# MakerCard.net
KiCad netlist of a schematic drawn in Altium Designer
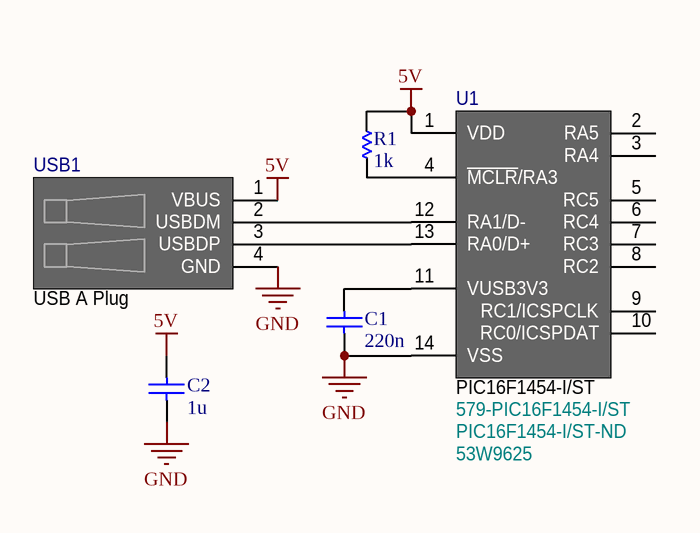
[diagram p0: MakerCard.SchDoc]

(export (version "E")
  (design (tool "Eeschema 10.0.6"))
  (components
    (comp (ref "C1")
      (value "220n")
      (footprint "CAPC1005N")
      (description "Capacitor (Semiconductor SIM Model)")
      (fields (field (name "PUBLISHER") "Altium Limited"))
      (libsource (lib "Miscellaneous Devices") (part "Cap Semi"))
    )
    (comp (ref "C2")
      (value "1u")
      (footprint "CAPC1608N")
      (description "Capacitor (Semiconductor SIM Model)")
      (fields (field (name "PUBLISHER") "Altium Limited"))
      (libsource (lib "Miscellaneous Devices") (part "Cap Semi"))
    )
    (comp (ref "R1")
      (value "1k")
      (footprint "RESC1005N")
      (description "Semiconductor Resistor")
      (fields (field (name "PUBLISHER") "Altium Limited"))
      (libsource (lib "Miscellaneous Devices") (part "Res Semi"))
    )
    (comp (ref "U1")
      (value "PIC16F1454-I/ST")
      (footprint "TSOP65P640-14AN")
      (description "8-bit Microcontrollers - MCU 7 KB Flash 512 bytes RAM 48 MHz Int Osc")
      (fields
        (field (name "MANUFACTURER") "Microchip Technology")
        (field (name "SUPPLIER PART NUMBER 1") "579-PIC16F1454-I/ST")
        (field (name "SUPPLIER PART NUMBER 2") "PIC16F1454-I/ST-ND")
        (field (name "SUPPLIER PART NUMBER 3") "53W9625")
      )
      (libsource (lib "Microchip Microcontroller 8-Bit") (part "PIC16F1454-I/ST"))
    )
    (comp (ref "USB1")
      (value "USB A Plug")
      (footprint "USB_A_EDGECONNECTOR")
      (libsource (lib "Miscellaneous Connectors") (part "USB A Plug"))
    )
  )
  (nets
    (net (code "1") (name "5V") (class "Default")
      (node (ref "C2") (pin "2") (pinfunction "2_2") (pintype "passive"))
      (node (ref "R1") (pin "2") (pinfunction "2_2") (pintype "passive"))
      (node (ref "U1") (pin "1") (pinfunction "VDD_1") (pintype "power_in"))
      (node (ref "USB1") (pin "1") (pinfunction "VBUS_1") (pintype "power_in"))
    )
    (net (code "2") (name "GND") (class "Default")
      (node (ref "C1") (pin "1") (pinfunction "1_1") (pintype "passive"))
      (node (ref "C2") (pin "1") (pinfunction "1_1") (pintype "passive"))
      (node (ref "U1") (pin "14") (pinfunction "VSS_14") (pintype "power_in"))
      (node (ref "USB1") (pin "4") (pinfunction "GND_4") (pintype "power_in"))
    )
    (net (code "3") (name "Net-(U1-RA0{slash}D+)") (class "Default")
      (node (ref "U1") (pin "13") (pinfunction "RA0/D+_13") (pintype "power_in"))
      (node (ref "USB1") (pin "3") (pinfunction "USBDP_3") (pintype "power_in"))
    )
    (net (code "4") (name "Net-(U1-RA1{slash}D-)") (class "Default")
      (node (ref "U1") (pin "12") (pinfunction "RA1/D-_12") (pintype "power_in"))
      (node (ref "USB1") (pin "2") (pinfunction "USBDM_2") (pintype "power_in"))
    )
    (net (code "5") (name "Net-(U1-VUSB3V3)") (class "Default")
      (node (ref "C1") (pin "2") (pinfunction "2_2") (pintype "passive"))
      (node (ref "U1") (pin "11") (pinfunction "VUSB3V3_11") (pintype "power_in"))
    )
    (net (code "6") (name "Net-(U1-~{MCLR}{slash}RA3)") (class "Default")
      (node (ref "R1") (pin "1") (pinfunction "1_1") (pintype "passive"))
      (node (ref "U1") (pin "4") (pinfunction "~{MCLR}/RA3_4") (pintype "power_in"))
    )
    (net (code "7") (name "unconnected-(U1-RA4-Pad3)") (class "Default")
      (node (ref "U1") (pin "3") (pinfunction "RA4_3") (pintype "power_in"))
    )
    (net (code "8") (name "unconnected-(U1-RA5-Pad2)") (class "Default")
      (node (ref "U1") (pin "2") (pinfunction "RA5_2") (pintype "power_in"))
    )
    (net (code "9") (name "unconnected-(U1-RC0{slash}ICSPDAT-Pad10)") (class "Default")
      (node (ref "U1") (pin "10") (pinfunction "RC0/ICSPDAT_10") (pintype "power_in"))
    )
    (net (code "10") (name "unconnected-(U1-RC1{slash}ICSPCLK-Pad9)") (class "Default")
      (node (ref "U1") (pin "9") (pinfunction "RC1/ICSPCLK_9") (pintype "power_in"))
    )
    (net (code "11") (name "unconnected-(U1-RC2-Pad8)") (class "Default")
      (node (ref "U1") (pin "8") (pinfunction "RC2_8") (pintype "power_in"))
    )
    (net (code "12") (name "unconnected-(U1-RC3-Pad7)") (class "Default")
      (node (ref "U1") (pin "7") (pinfunction "RC3_7") (pintype "power_in"))
    )
    (net (code "13") (name "unconnected-(U1-RC4-Pad6)") (class "Default")
      (node (ref "U1") (pin "6") (pinfunction "RC4_6") (pintype "power_in"))
    )
    (net (code "14") (name "unconnected-(U1-RC5-Pad5)") (class "Default")
      (node (ref "U1") (pin "5") (pinfunction "RC5_5") (pintype "power_in"))
    )
  )
)
